# Shied_Array_Sensor.net
KiCad netlist of a schematic drawn in EAGLE
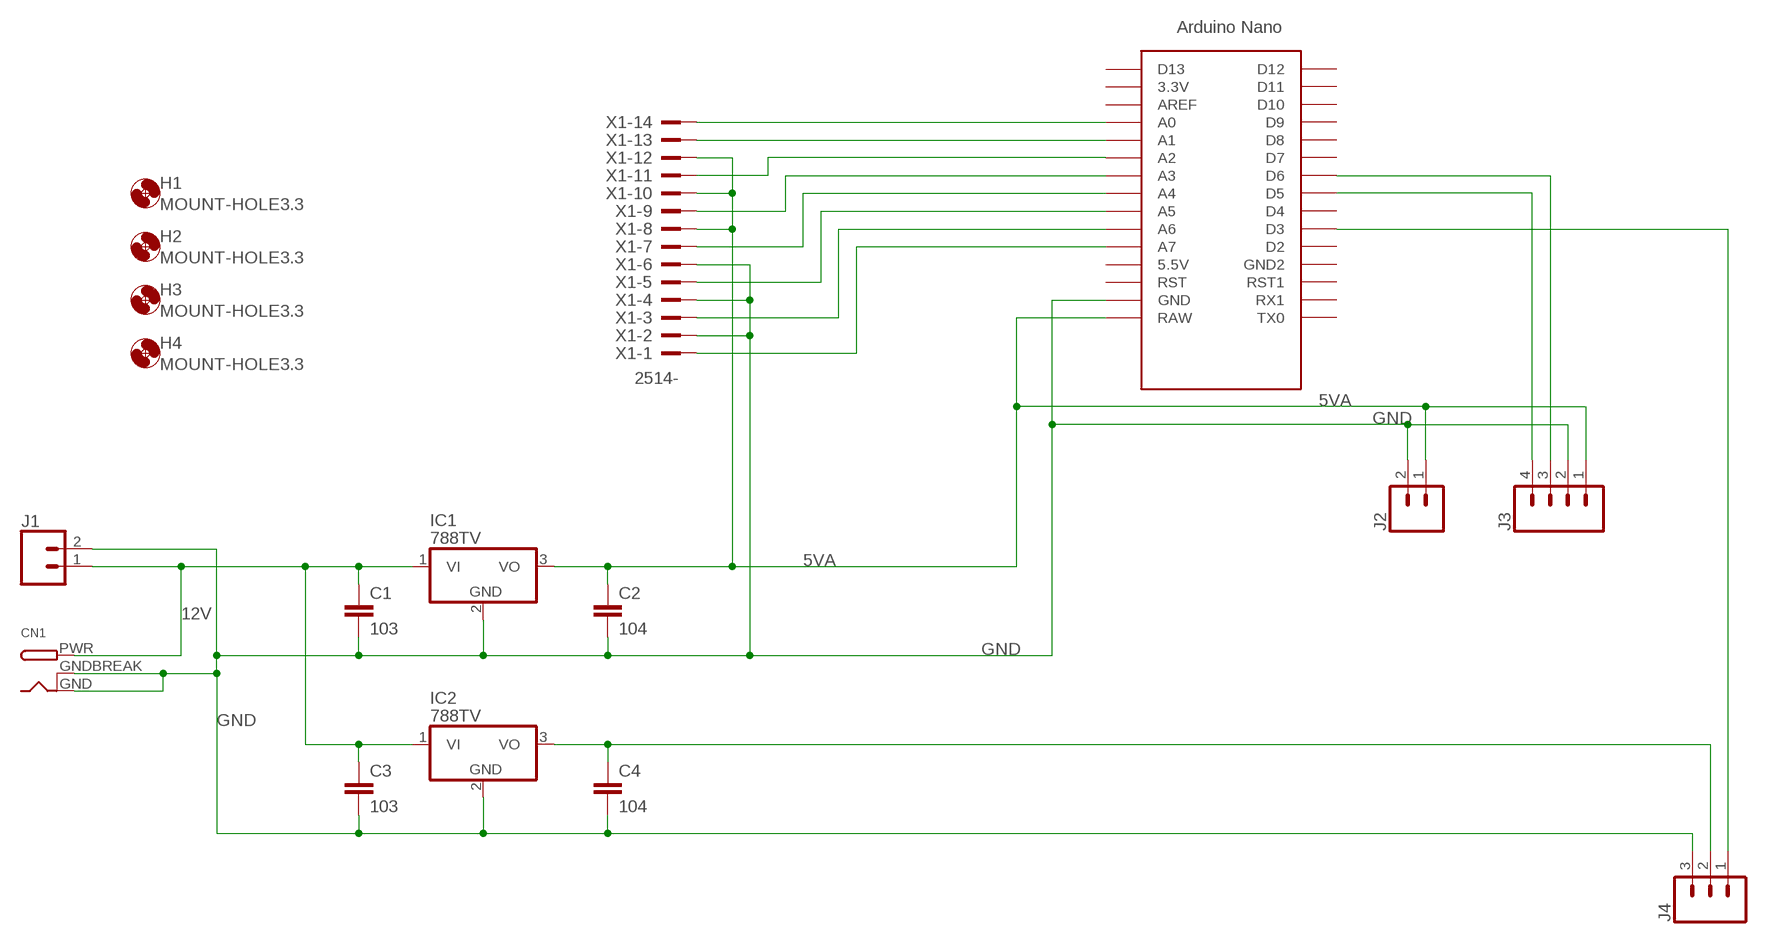
[diagram p0: schematic, sheet 1]

(export (version "E")
  (design (tool "Eeschema 10.0.6"))
  (components
    (comp (ref "C1")
      (value "103")
      (footprint "eagle-import:C050-024X044")
      (libsource (lib "eagle-import") (part "C-EU050-024X044"))
    )
    (comp (ref "C2")
      (value "104")
      (footprint "eagle-import:C050-024X044")
      (libsource (lib "eagle-import") (part "C-EU050-024X044"))
    )
    (comp (ref "C3")
      (value "103")
      (footprint "eagle-import:C050-024X044")
      (libsource (lib "eagle-import") (part "C-EU050-024X044"))
    )
    (comp (ref "C4")
      (value "104")
      (footprint "eagle-import:C050-024X044")
      (libsource (lib "eagle-import") (part "C-EU050-024X044"))
    )
    (comp (ref "CN1")
      (value "DCBARRELPTH")
      (footprint "eagle-import:DCJACK_2MM_PTH")
      (libsource (lib "eagle-import") (part "DCBARRELPTH"))
    )
    (comp (ref "H1")
      (value "MOUNT-HOLE3.3")
      (footprint "eagle-import:3,3")
      (libsource (lib "eagle-import") (part "MOUNT-HOLE3.3"))
    )
    (comp (ref "H2")
      (value "MOUNT-HOLE3.3")
      (footprint "eagle-import:3,3")
      (libsource (lib "eagle-import") (part "MOUNT-HOLE3.3"))
    )
    (comp (ref "H3")
      (value "MOUNT-HOLE3.3")
      (footprint "eagle-import:3,3")
      (libsource (lib "eagle-import") (part "MOUNT-HOLE3.3"))
    )
    (comp (ref "H4")
      (value "MOUNT-HOLE3.3")
      (footprint "eagle-import:3,3")
      (libsource (lib "eagle-import") (part "MOUNT-HOLE3.3"))
    )
    (comp (ref "IC1")
      (value "788TV")
      (footprint "eagle-import:TO220V")
      (libsource (lib "eagle-import") (part "78TV8"))
    )
    (comp (ref "IC2")
      (value "788TV")
      (footprint "eagle-import:TO220V")
      (libsource (lib "eagle-import") (part "78TV8"))
    )
    (comp (ref "J1")
      (value "CONN_023.5MM_LOCK")
      (footprint "eagle-import:SCREWTERMINAL-3.5MM-2_LOCK")
      (libsource (lib "eagle-import") (part "CONN_023.5MM_LOCK"))
    )
    (comp (ref "J2")
      (value "CONN_023.5MM_LOCK")
      (footprint "eagle-import:SCREWTERMINAL-3.5MM-2_LOCK")
      (libsource (lib "eagle-import") (part "CONN_023.5MM_LOCK"))
    )
    (comp (ref "J3")
      (value "CONN_04LONGPADS")
      (footprint "eagle-import:1X04_LONGPADS")
      (libsource (lib "eagle-import") (part "CONN_04LONGPADS"))
    )
    (comp (ref "J4")
      (value "CONN_03LONGPADS")
      (footprint "eagle-import:1X03_LONGPADS")
      (libsource (lib "eagle-import") (part "CONN_03LONGPADS"))
    )
    (comp (ref "U$1")
      (value "NANO")
      (footprint "eagle-import:NANO")
      (libsource (lib "eagle-import") (part "NANO"))
    )
    (comp (ref "X1")
      (value "2514-")
      (footprint "eagle-import:PAK100_2500-14")
      (libsource (lib "eagle-import") (part "2514-"))
    )
  )
  (nets
    (net (code "1") (name "/5VA") (class "Default")
      (node (ref "C2") (pin "1") (pinfunction "1_1") (pintype "passive"))
      (node (ref "IC1") (pin "3") (pinfunction "VO_3") (pintype "passive"))
      (node (ref "J2") (pin "1") (pinfunction "1_1") (pintype "passive"))
      (node (ref "J3") (pin "1") (pinfunction "1_1") (pintype "passive"))
      (node (ref "U$1") (pin "RAW") (pinfunction "RAW_RAW") (pintype "bidirectional"))
      (node (ref "X1") (pin "10") (pinfunction "KL_10") (pintype "passive"))
      (node (ref "X1") (pin "12") (pinfunction "KL_12") (pintype "passive"))
      (node (ref "X1") (pin "8") (pinfunction "KL_8") (pintype "passive"))
    )
    (net (code "2") (name "/12V") (class "Default")
      (node (ref "C1") (pin "1") (pinfunction "1_1") (pintype "passive"))
      (node (ref "C3") (pin "1") (pinfunction "1_1") (pintype "passive"))
      (node (ref "CN1") (pin "PWR") (pinfunction "PWR_PWR") (pintype "power_in"))
      (node (ref "IC1") (pin "1") (pinfunction "VI_1") (pintype "input"))
      (node (ref "IC2") (pin "1") (pinfunction "VI_1") (pintype "input"))
      (node (ref "J1") (pin "1") (pinfunction "1_1") (pintype "passive"))
    )
    (net (code "3") (name "/GND") (class "Default")
      (node (ref "C1") (pin "2") (pinfunction "2_2") (pintype "passive"))
      (node (ref "C2") (pin "2") (pinfunction "2_2") (pintype "passive"))
      (node (ref "C3") (pin "2") (pinfunction "2_2") (pintype "passive"))
      (node (ref "C4") (pin "2") (pinfunction "2_2") (pintype "passive"))
      (node (ref "CN1") (pin "GND") (pinfunction "GND_GND") (pintype "power_in"))
      (node (ref "CN1") (pin "GNDBREAK") (pinfunction "GNDBREAK_GNDBREAK") (pintype "power_in"))
      (node (ref "IC1") (pin "2") (pinfunction "GND_2") (pintype "passive"))
      (node (ref "IC2") (pin "2") (pinfunction "GND_2") (pintype "passive"))
      (node (ref "J1") (pin "2") (pinfunction "2_2") (pintype "passive"))
      (node (ref "J2") (pin "2") (pinfunction "2_2") (pintype "passive"))
      (node (ref "J3") (pin "2") (pinfunction "2_2") (pintype "passive"))
      (node (ref "J4") (pin "3") (pinfunction "3_3") (pintype "passive"))
      (node (ref "U$1") (pin "GND") (pinfunction "GND_GND") (pintype "bidirectional"))
      (node (ref "X1") (pin "2") (pinfunction "KL_2") (pintype "passive"))
      (node (ref "X1") (pin "4") (pinfunction "KL_4") (pintype "passive"))
      (node (ref "X1") (pin "6") (pinfunction "KL_6") (pintype "passive"))
    )
    (net (code "4") (name "Net-(IC2-VO)") (class "Default")
      (node (ref "C4") (pin "1") (pinfunction "1_1") (pintype "passive"))
      (node (ref "IC2") (pin "3") (pinfunction "VO_3") (pintype "passive"))
      (node (ref "J4") (pin "2") (pinfunction "2_2") (pintype "passive"))
    )
    (net (code "5") (name "Net-(J3-Pad3)") (class "Default")
      (node (ref "J3") (pin "3") (pinfunction "3_3") (pintype "passive"))
      (node (ref "U$1") (pin "D6") (pinfunction "D6_D6") (pintype "bidirectional"))
    )
    (net (code "6") (name "Net-(J3-Pad4)") (class "Default")
      (node (ref "J3") (pin "4") (pinfunction "4_4") (pintype "passive"))
      (node (ref "U$1") (pin "D5") (pinfunction "D5_D5") (pintype "bidirectional"))
    )
    (net (code "7") (name "Net-(J4-Pad1)") (class "Default")
      (node (ref "J4") (pin "1") (pinfunction "1_1") (pintype "passive"))
      (node (ref "U$1") (pin "D3") (pinfunction "D3_D3") (pintype "bidirectional"))
    )
    (net (code "8") (name "Net-(X1A-KL)") (class "Default")
      (node (ref "U$1") (pin "A7") (pinfunction "A7_A7") (pintype "bidirectional"))
      (node (ref "X1") (pin "1") (pinfunction "KL_1") (pintype "passive"))
    )
    (net (code "9") (name "Net-(X1C-KL)") (class "Default")
      (node (ref "U$1") (pin "A2") (pinfunction "A2_A2") (pintype "bidirectional"))
      (node (ref "X1") (pin "11") (pinfunction "KL_11") (pintype "passive"))
    )
    (net (code "10") (name "Net-(X1E-KL)") (class "Default")
      (node (ref "U$1") (pin "A1") (pinfunction "A1_A1") (pintype "bidirectional"))
      (node (ref "X1") (pin "13") (pinfunction "KL_13") (pintype "passive"))
    )
    (net (code "11") (name "Net-(X1F-KL)") (class "Default")
      (node (ref "U$1") (pin "A0") (pinfunction "A0_A0") (pintype "bidirectional"))
      (node (ref "X1") (pin "14") (pinfunction "KL_14") (pintype "passive"))
    )
    (net (code "12") (name "Net-(X1H-KL)") (class "Default")
      (node (ref "U$1") (pin "A6") (pinfunction "A6_A6") (pintype "bidirectional"))
      (node (ref "X1") (pin "3") (pinfunction "KL_3") (pintype "passive"))
    )
    (net (code "13") (name "Net-(X1J-KL)") (class "Default")
      (node (ref "U$1") (pin "A5") (pinfunction "A5_A5") (pintype "bidirectional"))
      (node (ref "X1") (pin "5") (pinfunction "KL_5") (pintype "passive"))
    )
    (net (code "14") (name "Net-(X1L-KL)") (class "Default")
      (node (ref "U$1") (pin "A4") (pinfunction "A4_A4") (pintype "bidirectional"))
      (node (ref "X1") (pin "7") (pinfunction "KL_7") (pintype "passive"))
    )
    (net (code "15") (name "Net-(X1N-KL)") (class "Default")
      (node (ref "U$1") (pin "A3") (pinfunction "A3_A3") (pintype "bidirectional"))
      (node (ref "X1") (pin "9") (pinfunction "KL_9") (pintype "passive"))
    )
    (net (code "16") (name "unconnected-(U$1-5.5V-Pad5V)") (class "Default")
      (node (ref "U$1") (pin "5V") (pinfunction "5.5V_5V") (pintype "bidirectional"))
    )
    (net (code "17") (name "unconnected-(U$1-GND2-PadGND1)") (class "Default")
      (node (ref "U$1") (pin "GND1") (pinfunction "GND2_GND1") (pintype "bidirectional"))
    )
    (net (code "18") (name "unconnected-(U$1-Pad3.3V)") (class "Default")
      (node (ref "U$1") (pin "3.3V") (pinfunction "3.3V_3.3V") (pintype "bidirectional"))
    )
    (net (code "19") (name "unconnected-(U$1-PadAREF)") (class "Default")
      (node (ref "U$1") (pin "AREF") (pinfunction "AREF_AREF") (pintype "bidirectional"))
    )
    (net (code "20") (name "unconnected-(U$1-PadD2)") (class "Default")
      (node (ref "U$1") (pin "D2") (pinfunction "D2_D2") (pintype "bidirectional"))
    )
    (net (code "21") (name "unconnected-(U$1-PadD4)") (class "Default")
      (node (ref "U$1") (pin "D4") (pinfunction "D4_D4") (pintype "bidirectional"))
    )
    (net (code "22") (name "unconnected-(U$1-PadD7)") (class "Default")
      (node (ref "U$1") (pin "D7") (pinfunction "D7_D7") (pintype "bidirectional"))
    )
    (net (code "23") (name "unconnected-(U$1-PadD8)") (class "Default")
      (node (ref "U$1") (pin "D8") (pinfunction "D8_D8") (pintype "bidirectional"))
    )
    (net (code "24") (name "unconnected-(U$1-PadD9)") (class "Default")
      (node (ref "U$1") (pin "D9") (pinfunction "D9_D9") (pintype "bidirectional"))
    )
    (net (code "25") (name "unconnected-(U$1-PadD10)") (class "Default")
      (node (ref "U$1") (pin "D10") (pinfunction "D10_D10") (pintype "bidirectional"))
    )
    (net (code "26") (name "unconnected-(U$1-PadD11)") (class "Default")
      (node (ref "U$1") (pin "D11") (pinfunction "D11_D11") (pintype "bidirectional"))
    )
    (net (code "27") (name "unconnected-(U$1-PadD12)") (class "Default")
      (node (ref "U$1") (pin "D12") (pinfunction "D12_D12") (pintype "bidirectional"))
    )
    (net (code "28") (name "unconnected-(U$1-PadD13)") (class "Default")
      (node (ref "U$1") (pin "D13") (pinfunction "D13_D13") (pintype "bidirectional"))
    )
    (net (code "29") (name "unconnected-(U$1-PadICSP1)") (class "Default")
      (node (ref "U$1") (pin "ICSP1") (pinfunction "ICSP1_ICSP1") (pintype "bidirectional"))
    )
    (net (code "30") (name "unconnected-(U$1-PadICSP2)") (class "Default")
      (node (ref "U$1") (pin "ICSP2") (pinfunction "ICSP2_ICSP2") (pintype "bidirectional"))
    )
    (net (code "31") (name "unconnected-(U$1-PadICSP3)") (class "Default")
      (node (ref "U$1") (pin "ICSP3") (pinfunction "ICSP3_ICSP3") (pintype "bidirectional"))
    )
    (net (code "32") (name "unconnected-(U$1-PadICSP4)") (class "Default")
      (node (ref "U$1") (pin "ICSP4") (pinfunction "ICSP4_ICSP4") (pintype "bidirectional"))
    )
    (net (code "33") (name "unconnected-(U$1-PadICSP5)") (class "Default")
      (node (ref "U$1") (pin "ICSP5") (pinfunction "ICSP5_ICSP5") (pintype "bidirectional"))
    )
    (net (code "34") (name "unconnected-(U$1-PadICSP6)") (class "Default")
      (node (ref "U$1") (pin "ICSP6") (pinfunction "ICSP6_ICSP6") (pintype "bidirectional"))
    )
    (net (code "35") (name "unconnected-(U$1-PadRST)") (class "Default")
      (node (ref "U$1") (pin "RST") (pinfunction "RST_RST") (pintype "bidirectional"))
    )
    (net (code "36") (name "unconnected-(U$1-PadRST1)") (class "Default")
      (node (ref "U$1") (pin "RST1") (pinfunction "RST1_RST1") (pintype "bidirectional"))
    )
    (net (code "37") (name "unconnected-(U$1-PadRX1)") (class "Default")
      (node (ref "U$1") (pin "RX1") (pinfunction "RX1_RX1") (pintype "bidirectional"))
    )
    (net (code "38") (name "unconnected-(U$1-PadTX0)") (class "Default")
      (node (ref "U$1") (pin "TX0") (pinfunction "TX0_TX0") (pintype "bidirectional"))
    )
  )
)
